# Digital_Camera.net
KiCad netlist of a schematic drawn in Altium Designer
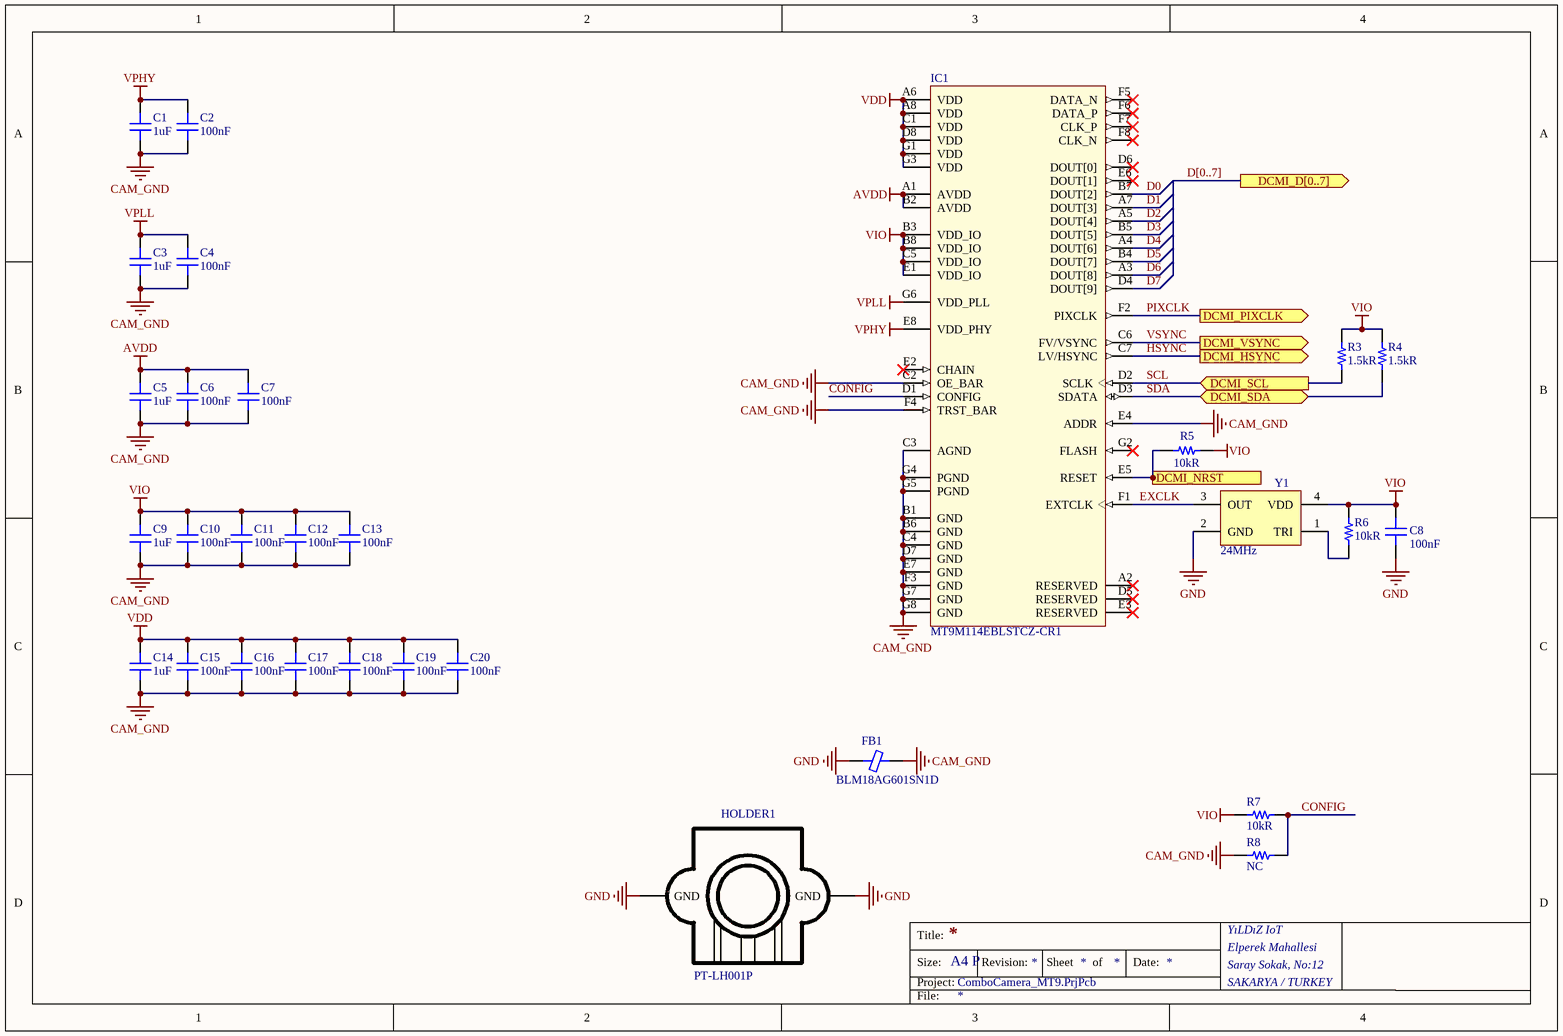
[diagram p0: Digital Camera.SchDoc]

(export (version "E")
  (design (tool "Eeschema 10.0.6"))
  (components
    (comp (ref "C1")
      (value "1uF")
      (footprint "CAP 0603/1608")
      (description "Ceramic, SMT Capacitor")
      (fields
        (field (name "MANUFACTURER") "Samsung")
        (field (name "MANUFACTURER PART NUMBER") "CL10A105KP8NNNC")
      )
      (libsource (lib "yildizIoT Library") (part "Capacitor - Ceramic"))
    )
    (comp (ref "C2")
      (value "100nF")
      (footprint "CAP 0603/1608")
      (description "Ceramic, SMT Capacitor")
      (fields
        (field (name "MANUFACTURER") "Samsung")
        (field (name "MANUFACTURER PART NUMBER") "CL10B104JB8NNNC")
      )
      (libsource (lib "yildizIoT Library") (part "Capacitor - Ceramic"))
    )
    (comp (ref "C3")
      (value "1uF")
      (footprint "CAP 0603/1608")
      (description "Ceramic, SMT Capacitor")
      (fields
        (field (name "MANUFACTURER") "Samsung")
        (field (name "MANUFACTURER PART NUMBER") "CL10A105KP8NNNC")
      )
      (libsource (lib "yildizIoT Library") (part "Capacitor - Ceramic"))
    )
    (comp (ref "C4")
      (value "100nF")
      (footprint "CAP 0603/1608")
      (description "Ceramic, SMT Capacitor")
      (fields
        (field (name "MANUFACTURER") "Samsung")
        (field (name "MANUFACTURER PART NUMBER") "CL10B104JB8NNNC")
      )
      (libsource (lib "yildizIoT Library") (part "Capacitor - Ceramic"))
    )
    (comp (ref "C5")
      (value "1uF")
      (footprint "CAP 0603/1608")
      (description "Ceramic, SMT Capacitor")
      (fields
        (field (name "MANUFACTURER") "Samsung")
        (field (name "MANUFACTURER PART NUMBER") "CL10A105KP8NNNC")
      )
      (libsource (lib "yildizIoT Library") (part "Capacitor - Ceramic"))
    )
    (comp (ref "C6")
      (value "100nF")
      (footprint "CAP 0603/1608")
      (description "Ceramic, SMT Capacitor")
      (fields
        (field (name "MANUFACTURER") "Samsung")
        (field (name "MANUFACTURER PART NUMBER") "CL10B104JB8NNNC")
      )
      (libsource (lib "yildizIoT Library") (part "Capacitor - Ceramic"))
    )
    (comp (ref "C7")
      (value "100nF")
      (footprint "CAP 0603/1608")
      (description "Ceramic, SMT Capacitor")
      (fields
        (field (name "MANUFACTURER") "Samsung")
        (field (name "MANUFACTURER PART NUMBER") "CL10B104JB8NNNC")
      )
      (libsource (lib "yildizIoT Library") (part "Capacitor - Ceramic"))
    )
    (comp (ref "C8")
      (value "100nF")
      (footprint "CAP 0603/1608")
      (description "Ceramic, SMT Capacitor")
      (fields
        (field (name "MANUFACTURER") "Samsung")
        (field (name "MANUFACTURER PART NUMBER") "CL10B104JB8NNNC")
      )
      (libsource (lib "yildizIoT Library") (part "Capacitor - Ceramic"))
    )
    (comp (ref "C9")
      (value "1uF")
      (footprint "CAP 0603/1608")
      (description "Ceramic, SMT Capacitor")
      (fields
        (field (name "MANUFACTURER") "Samsung")
        (field (name "MANUFACTURER PART NUMBER") "CL10A105KP8NNNC")
      )
      (libsource (lib "yildizIoT Library") (part "Capacitor - Ceramic"))
    )
    (comp (ref "C10")
      (value "100nF")
      (footprint "CAP 0603/1608")
      (description "Ceramic, SMT Capacitor")
      (fields
        (field (name "MANUFACTURER") "Samsung")
        (field (name "MANUFACTURER PART NUMBER") "CL10B104JB8NNNC")
      )
      (libsource (lib "yildizIoT Library") (part "Capacitor - Ceramic"))
    )
    (comp (ref "C11")
      (value "100nF")
      (footprint "CAP 0603/1608")
      (description "Ceramic, SMT Capacitor")
      (fields
        (field (name "MANUFACTURER") "Samsung")
        (field (name "MANUFACTURER PART NUMBER") "CL10B104JB8NNNC")
      )
      (libsource (lib "yildizIoT Library") (part "Capacitor - Ceramic"))
    )
    (comp (ref "C12")
      (value "100nF")
      (footprint "CAP 0603/1608")
      (description "Ceramic, SMT Capacitor")
      (fields
        (field (name "MANUFACTURER") "Samsung")
        (field (name "MANUFACTURER PART NUMBER") "CL10B104JB8NNNC")
      )
      (libsource (lib "yildizIoT Library") (part "Capacitor - Ceramic"))
    )
    (comp (ref "C13")
      (value "100nF")
      (footprint "CAP 0603/1608")
      (description "Ceramic, SMT Capacitor")
      (fields
        (field (name "MANUFACTURER") "Samsung")
        (field (name "MANUFACTURER PART NUMBER") "CL10B104JB8NNNC")
      )
      (libsource (lib "yildizIoT Library") (part "Capacitor - Ceramic"))
    )
    (comp (ref "C14")
      (value "1uF")
      (footprint "CAP 0603/1608")
      (description "Ceramic, SMT Capacitor")
      (fields
        (field (name "MANUFACTURER") "Samsung")
        (field (name "MANUFACTURER PART NUMBER") "CL10A105KP8NNNC")
      )
      (libsource (lib "yildizIoT Library") (part "Capacitor - Ceramic"))
    )
    (comp (ref "C15")
      (value "100nF")
      (footprint "CAP 0603/1608")
      (description "Ceramic, SMT Capacitor")
      (fields
        (field (name "MANUFACTURER") "Samsung")
        (field (name "MANUFACTURER PART NUMBER") "CL10B104JB8NNNC")
      )
      (libsource (lib "yildizIoT Library") (part "Capacitor - Ceramic"))
    )
    (comp (ref "C16")
      (value "100nF")
      (footprint "CAP 0603/1608")
      (description "Ceramic, SMT Capacitor")
      (fields
        (field (name "MANUFACTURER") "Samsung")
        (field (name "MANUFACTURER PART NUMBER") "CL10B104JB8NNNC")
      )
      (libsource (lib "yildizIoT Library") (part "Capacitor - Ceramic"))
    )
    (comp (ref "C17")
      (value "100nF")
      (footprint "CAP 0603/1608")
      (description "Ceramic, SMT Capacitor")
      (fields
        (field (name "MANUFACTURER") "Samsung")
        (field (name "MANUFACTURER PART NUMBER") "CL10B104JB8NNNC")
      )
      (libsource (lib "yildizIoT Library") (part "Capacitor - Ceramic"))
    )
    (comp (ref "C18")
      (value "100nF")
      (footprint "CAP 0603/1608")
      (description "Ceramic, SMT Capacitor")
      (fields
        (field (name "MANUFACTURER") "Samsung")
        (field (name "MANUFACTURER PART NUMBER") "CL10B104JB8NNNC")
      )
      (libsource (lib "yildizIoT Library") (part "Capacitor - Ceramic"))
    )
    (comp (ref "C19")
      (value "100nF")
      (footprint "CAP 0603/1608")
      (description "Ceramic, SMT Capacitor")
      (fields
        (field (name "MANUFACTURER") "Samsung")
        (field (name "MANUFACTURER PART NUMBER") "CL10B104JB8NNNC")
      )
      (libsource (lib "yildizIoT Library") (part "Capacitor - Ceramic"))
    )
    (comp (ref "C20")
      (value "100nF")
      (footprint "CAP 0603/1608")
      (description "Ceramic, SMT Capacitor")
      (fields
        (field (name "MANUFACTURER") "Samsung")
        (field (name "MANUFACTURER PART NUMBER") "CL10B104JB8NNNC")
      )
      (libsource (lib "yildizIoT Library") (part "Capacitor - Ceramic"))
    )
    (comp (ref "FB1")
      (value "BLM18AG601SN1D")
      (footprint "FER 0603/1608")
      (description "SMT Ferrite Chip")
      (fields (field (name "MANUFACTURER") "Murata") (field (name "TOLERANCE") "25%"))
      (libsource (lib "yildizIoT Library") (part "Ferrite Chip"))
    )
    (comp (ref "HOLDER1")
      (value "PT-LH001P")
      (footprint "M12 LENS HOLDER")
      (libsource (lib "yildizIoT Library") (part "LENS HOLDER"))
    )
    (comp (ref "IC1")
      (value "MT9M114EBLSTCZ-CR1")
      (footprint "ON SEMI MT9M114 BGA-55")
      (description "1/6‐inch 720p High‐Definition (HD) System‐On‐a‐Chip (SOC) Digital Image Sensor")
      (fields (field (name "MANUFACTURER") "ON Semiconductor"))
      (libsource (lib "yildizIoT Library") (part "ON SEMI MT9M114"))
    )
    (comp (ref "R3")
      (value "1.5kR")
      (footprint "RES 0603/1608")
      (description "Ceramic, SMT Capacitor")
      (fields
        (field (name "MANUFACTURER") "Yageo")
        (field (name "MANUFACTURER PART NUMBER") "RC0603FR-071K5L")
      )
      (libsource (lib "yildizIoT Library") (part "Resistor_Chip"))
    )
    (comp (ref "R4")
      (value "1.5kR")
      (footprint "RES 0603/1608")
      (description "Ceramic, SMT Capacitor")
      (fields
        (field (name "MANUFACTURER") "Yageo")
        (field (name "MANUFACTURER PART NUMBER") "RC0603FR-071K5L")
      )
      (libsource (lib "yildizIoT Library") (part "Resistor_Chip"))
    )
    (comp (ref "R5")
      (value "10kR")
      (footprint "RES 0603/1608")
      (description "Ceramic, SMT Capacitor")
      (fields
        (field (name "MANUFACTURER") "Stackpole Electronics")
        (field (name "MANUFACTURER PART NUMBER") "RNCP0603FTD10K0")
      )
      (libsource (lib "yildizIoT Library") (part "Resistor_Chip"))
    )
    (comp (ref "R6")
      (value "10kR")
      (footprint "RES 0603/1608")
      (description "Ceramic, SMT Capacitor")
      (fields
        (field (name "MANUFACTURER") "Stackpole Electronics")
        (field (name "MANUFACTURER PART NUMBER") "RNCP0603FTD10K0")
      )
      (libsource (lib "yildizIoT Library") (part "Resistor_Chip"))
    )
    (comp (ref "R7")
      (value "10kR")
      (footprint "RES 0603/1608")
      (description "Ceramic, SMT Capacitor")
      (fields
        (field (name "MANUFACTURER") "Stackpole Electronics")
        (field (name "MANUFACTURER PART NUMBER") "RNCP0603FTD10K0")
      )
      (libsource (lib "yildizIoT Library") (part "Resistor_Chip"))
    )
    (comp (ref "R8")
      (value "10kR")
      (footprint "RES 0603/1608")
      (description "Ceramic, SMT Capacitor")
      (fields
        (field (name "MANUFACTURER") "Stackpole Electronics")
        (field (name "MANUFACTURER PART NUMBER") "RNCP0603FTD10K0")
        (field (name "NC") "NC")
      )
      (libsource (lib "yildizIoT Library") (part "Resistor_Chip"))
    )
    (comp (ref "Y1")
      (value "24MHz")
      (footprint "Abracon ASTX-11")
      (description "OSC XO 1.544MHZ CMOS SMD")
      (fields
        (field (name "MANUFACTURER") "ECS Inc.")
        (field (name "MANUFACTURER PART NUMBER") "ECS-3225MV-240-CN-TR")
      )
      (libsource (lib "Celestial Library Database") (part "Abracon XO ASD"))
    )
  )
  (nets
    (net (code "1") (name "/CONFIG") (class "Default")
      (node (ref "IC1") (pin "D1") (pinfunction "CONFIG_D1") (pintype "input"))
      (node (ref "R7") (pin "2") (pinfunction "2_2") (pintype "passive"))
      (node (ref "R8") (pin "2") (pinfunction "2_2") (pintype "passive"))
    )
    (net (code "2") (name "/D0") (class "Default")
      (node (ref "IC1") (pin "B7") (pinfunction "DOUT[2]_B7") (pintype "output"))
    )
    (net (code "3") (name "/D1") (class "Default")
      (node (ref "IC1") (pin "A7") (pinfunction "DOUT[3]_A7") (pintype "output"))
    )
    (net (code "4") (name "/D2") (class "Default")
      (node (ref "IC1") (pin "A5") (pinfunction "DOUT[4]_A5") (pintype "output"))
    )
    (net (code "5") (name "/D3") (class "Default")
      (node (ref "IC1") (pin "B5") (pinfunction "DOUT[5]_B5") (pintype "output"))
    )
    (net (code "6") (name "/D4") (class "Default")
      (node (ref "IC1") (pin "A4") (pinfunction "DOUT[6]_A4") (pintype "output"))
    )
    (net (code "7") (name "/D5") (class "Default")
      (node (ref "IC1") (pin "B4") (pinfunction "DOUT[7]_B4") (pintype "output"))
    )
    (net (code "8") (name "/D6") (class "Default")
      (node (ref "IC1") (pin "A3") (pinfunction "DOUT[8]_A3") (pintype "output"))
    )
    (net (code "9") (name "/D7") (class "Default")
      (node (ref "IC1") (pin "D4") (pinfunction "DOUT[9]_D4") (pintype "output"))
    )
    (net (code "10") (name "/DCMI_NRST") (class "Default")
      (node (ref "IC1") (pin "E5") (pinfunction "RESET_E5") (pintype "input"))
      (node (ref "R5") (pin "2") (pinfunction "2_2") (pintype "passive"))
    )
    (net (code "12") (name "/EXCLK") (class "Default")
      (node (ref "IC1") (pin "F1") (pinfunction "EXTCLK_F1") (pintype "input"))
      (node (ref "Y1") (pin "3") (pinfunction "OUT_3") (pintype "passive"))
    )
    (net (code "13") (name "/HSYNC") (class "Default")
      (node (ref "IC1") (pin "C7") (pinfunction "LV/HSYNC_C7") (pintype "output"))
    )
    (net (code "14") (name "/PIXCLK") (class "Default")
      (node (ref "IC1") (pin "F2") (pinfunction "PIXCLK_F2") (pintype "output"))
    )
    (net (code "15") (name "/SCL") (class "Default")
      (node (ref "IC1") (pin "D2") (pinfunction "SCLK_D2") (pintype "input"))
      (node (ref "R3") (pin "1") (pinfunction "1_1") (pintype "passive"))
    )
    (net (code "16") (name "/SDA") (class "Default")
      (node (ref "IC1") (pin "D3") (pinfunction "SDATA_D3") (pintype "bidirectional"))
      (node (ref "R4") (pin "1") (pinfunction "1_1") (pintype "passive"))
    )
    (net (code "17") (name "/VSYNC") (class "Default")
      (node (ref "IC1") (pin "C6") (pinfunction "FV/VSYNC_C6") (pintype "output"))
    )
    (net (code "18") (name "AVDD") (class "Default")
      (node (ref "C5") (pin "2") (pinfunction "2_2") (pintype "passive"))
      (node (ref "C6") (pin "2") (pinfunction "2_2") (pintype "passive"))
      (node (ref "C7") (pin "2") (pinfunction "2_2") (pintype "passive"))
      (node (ref "IC1") (pin "A1") (pinfunction "AVDD_A1") (pintype "passive"))
      (node (ref "IC1") (pin "B2") (pinfunction "AVDD_B2") (pintype "passive"))
    )
    (net (code "19") (name "CAM_GND") (class "Default")
      (node (ref "C1") (pin "1") (pinfunction "1_1") (pintype "passive"))
      (node (ref "C10") (pin "1") (pinfunction "1_1") (pintype "passive"))
      (node (ref "C11") (pin "1") (pinfunction "1_1") (pintype "passive"))
      (node (ref "C12") (pin "1") (pinfunction "1_1") (pintype "passive"))
      (node (ref "C13") (pin "1") (pinfunction "1_1") (pintype "passive"))
      (node (ref "C14") (pin "1") (pinfunction "1_1") (pintype "passive"))
      (node (ref "C15") (pin "1") (pinfunction "1_1") (pintype "passive"))
      (node (ref "C16") (pin "1") (pinfunction "1_1") (pintype "passive"))
      (node (ref "C17") (pin "1") (pinfunction "1_1") (pintype "passive"))
      (node (ref "C18") (pin "1") (pinfunction "1_1") (pintype "passive"))
      (node (ref "C19") (pin "1") (pinfunction "1_1") (pintype "passive"))
      (node (ref "C2") (pin "1") (pinfunction "1_1") (pintype "passive"))
      (node (ref "C20") (pin "1") (pinfunction "1_1") (pintype "passive"))
      (node (ref "C3") (pin "1") (pinfunction "1_1") (pintype "passive"))
      (node (ref "C4") (pin "1") (pinfunction "1_1") (pintype "passive"))
      (node (ref "C5") (pin "1") (pinfunction "1_1") (pintype "passive"))
      (node (ref "C6") (pin "1") (pinfunction "1_1") (pintype "passive"))
      (node (ref "C7") (pin "1") (pinfunction "1_1") (pintype "passive"))
      (node (ref "C9") (pin "1") (pinfunction "1_1") (pintype "passive"))
      (node (ref "FB1") (pin "1") (pinfunction "1_1") (pintype "passive"))
      (node (ref "IC1") (pin "B1") (pinfunction "GND_B1") (pintype "passive"))
      (node (ref "IC1") (pin "B6") (pinfunction "GND_B6") (pintype "passive"))
      (node (ref "IC1") (pin "C2") (pinfunction "OE_BAR_C2") (pintype "input"))
      (node (ref "IC1") (pin "C3") (pinfunction "AGND_C3") (pintype "passive"))
      (node (ref "IC1") (pin "C4") (pinfunction "GND_C4") (pintype "passive"))
      (node (ref "IC1") (pin "D7") (pinfunction "GND_D7") (pintype "passive"))
      (node (ref "IC1") (pin "E4") (pinfunction "ADDR_E4") (pintype "input"))
      (node (ref "IC1") (pin "E7") (pinfunction "GND_E7") (pintype "passive"))
      (node (ref "IC1") (pin "F3") (pinfunction "GND_F3") (pintype "passive"))
      (node (ref "IC1") (pin "F4") (pinfunction "TRST_BAR_F4") (pintype "input"))
      (node (ref "IC1") (pin "G4") (pinfunction "PGND_G4") (pintype "passive"))
      (node (ref "IC1") (pin "G5") (pinfunction "PGND_G5") (pintype "passive"))
      (node (ref "IC1") (pin "G7") (pinfunction "GND_G7") (pintype "passive"))
      (node (ref "IC1") (pin "G8") (pinfunction "GND_G8") (pintype "passive"))
      (node (ref "R8") (pin "1") (pinfunction "1_1") (pintype "passive"))
    )
    (net (code "20") (name "GND") (class "Default")
      (node (ref "C8") (pin "1") (pinfunction "1_1") (pintype "passive"))
      (node (ref "FB1") (pin "2") (pinfunction "2_2") (pintype "passive"))
      (node (ref "HOLDER1") (pin "GND") (pinfunction "GND_GND") (pintype "passive"))
      (node (ref "Y1") (pin "2") (pinfunction "GND_2") (pintype "passive"))
    )
    (net (code "21") (name "Net-(Y1-TRI)") (class "Default")
      (node (ref "R6") (pin "2") (pinfunction "2_2") (pintype "passive"))
      (node (ref "Y1") (pin "1") (pinfunction "TRI_1") (pintype "passive"))
    )
    (net (code "22") (name "VDD") (class "Default")
      (node (ref "C14") (pin "2") (pinfunction "2_2") (pintype "passive"))
      (node (ref "C15") (pin "2") (pinfunction "2_2") (pintype "passive"))
      (node (ref "C16") (pin "2") (pinfunction "2_2") (pintype "passive"))
      (node (ref "C17") (pin "2") (pinfunction "2_2") (pintype "passive"))
      (node (ref "C18") (pin "2") (pinfunction "2_2") (pintype "passive"))
      (node (ref "C19") (pin "2") (pinfunction "2_2") (pintype "passive"))
      (node (ref "C20") (pin "2") (pinfunction "2_2") (pintype "passive"))
      (node (ref "IC1") (pin "A6") (pinfunction "VDD_A6") (pintype "passive"))
      (node (ref "IC1") (pin "A8") (pinfunction "VDD_A8") (pintype "passive"))
      (node (ref "IC1") (pin "C1") (pinfunction "VDD_C1") (pintype "passive"))
      (node (ref "IC1") (pin "D8") (pinfunction "VDD_D8") (pintype "passive"))
      (node (ref "IC1") (pin "G1") (pinfunction "VDD_G1") (pintype "passive"))
      (node (ref "IC1") (pin "G3") (pinfunction "VDD_G3") (pintype "passive"))
    )
    (net (code "23") (name "VIO") (class "Default")
      (node (ref "C10") (pin "2") (pinfunction "2_2") (pintype "passive"))
      (node (ref "C11") (pin "2") (pinfunction "2_2") (pintype "passive"))
      (node (ref "C12") (pin "2") (pinfunction "2_2") (pintype "passive"))
      (node (ref "C13") (pin "2") (pinfunction "2_2") (pintype "passive"))
      (node (ref "C8") (pin "2") (pinfunction "2_2") (pintype "passive"))
      (node (ref "C9") (pin "2") (pinfunction "2_2") (pintype "passive"))
      (node (ref "IC1") (pin "B3") (pinfunction "VDD_IO_B3") (pintype "passive"))
      (node (ref "IC1") (pin "B8") (pinfunction "VDD_IO_B8") (pintype "passive"))
      (node (ref "IC1") (pin "C5") (pinfunction "VDD_IO_C5") (pintype "passive"))
      (node (ref "IC1") (pin "E1") (pinfunction "VDD_IO_E1") (pintype "passive"))
      (node (ref "R3") (pin "2") (pinfunction "2_2") (pintype "passive"))
      (node (ref "R4") (pin "2") (pinfunction "2_2") (pintype "passive"))
      (node (ref "R5") (pin "1") (pinfunction "1_1") (pintype "passive"))
      (node (ref "R6") (pin "1") (pinfunction "1_1") (pintype "passive"))
      (node (ref "R7") (pin "1") (pinfunction "1_1") (pintype "passive"))
      (node (ref "Y1") (pin "4") (pinfunction "VDD_4") (pintype "passive"))
    )
    (net (code "24") (name "VPHY") (class "Default")
      (node (ref "C1") (pin "2") (pinfunction "2_2") (pintype "passive"))
      (node (ref "C2") (pin "2") (pinfunction "2_2") (pintype "passive"))
      (node (ref "IC1") (pin "E8") (pinfunction "VDD_PHY_E8") (pintype "passive"))
    )
    (net (code "25") (name "VPLL") (class "Default")
      (node (ref "C3") (pin "2") (pinfunction "2_2") (pintype "passive"))
      (node (ref "C4") (pin "2") (pinfunction "2_2") (pintype "passive"))
      (node (ref "IC1") (pin "G6") (pinfunction "VDD_PLL_G6") (pintype "passive"))
    )
    (net (code "26") (name "unconnected-(IC1-CHAIN-PadE2)") (class "Default")
      (node (ref "IC1") (pin "E2") (pinfunction "CHAIN_E2") (pintype "input+no_connect"))
    )
    (net (code "27") (name "unconnected-(IC1-CLK_N-PadF8)") (class "Default")
      (node (ref "IC1") (pin "F8") (pinfunction "CLK_N_F8") (pintype "output+no_connect"))
    )
    (net (code "28") (name "unconnected-(IC1-CLK_P-PadF7)") (class "Default")
      (node (ref "IC1") (pin "F7") (pinfunction "CLK_P_F7") (pintype "output+no_connect"))
    )
    (net (code "29") (name "unconnected-(IC1-DATA_N-PadF5)") (class "Default")
      (node (ref "IC1") (pin "F5") (pinfunction "DATA_N_F5") (pintype "output+no_connect"))
    )
    (net (code "30") (name "unconnected-(IC1-DATA_P-PadF6)") (class "Default")
      (node (ref "IC1") (pin "F6") (pinfunction "DATA_P_F6") (pintype "output+no_connect"))
    )
    (net (code "31") (name "unconnected-(IC1-DOUT[0]-PadD6)") (class "Default")
      (node (ref "IC1") (pin "D6") (pinfunction "DOUT[0]_D6") (pintype "output+no_connect"))
    )
    (net (code "32") (name "unconnected-(IC1-DOUT[1]-PadE6)") (class "Default")
      (node (ref "IC1") (pin "E6") (pinfunction "DOUT[1]_E6") (pintype "output+no_connect"))
    )
    (net (code "33") (name "unconnected-(IC1-FLASH-PadG2)") (class "Default")
      (node (ref "IC1") (pin "G2") (pinfunction "FLASH_G2") (pintype "input+no_connect"))
    )
    (net (code "34") (name "unconnected-(IC1-RESERVED-PadA2)") (class "Default")
      (node (ref "IC1") (pin "A2") (pinfunction "RESERVED_A2") (pintype "passive+no_connect"))
    )
    (net (code "35") (name "unconnected-(IC1-RESERVED-PadD5)") (class "Default")
      (node (ref "IC1") (pin "D5") (pinfunction "RESERVED_D5") (pintype "passive+no_connect"))
    )
    (net (code "36") (name "unconnected-(IC1-RESERVED-PadE3)") (class "Default")
      (node (ref "IC1") (pin "E3") (pinfunction "RESERVED_E3") (pintype "passive+no_connect"))
    )
  )
)
